# Sheet1.net
KiCad netlist of a schematic drawn in Altium Designer
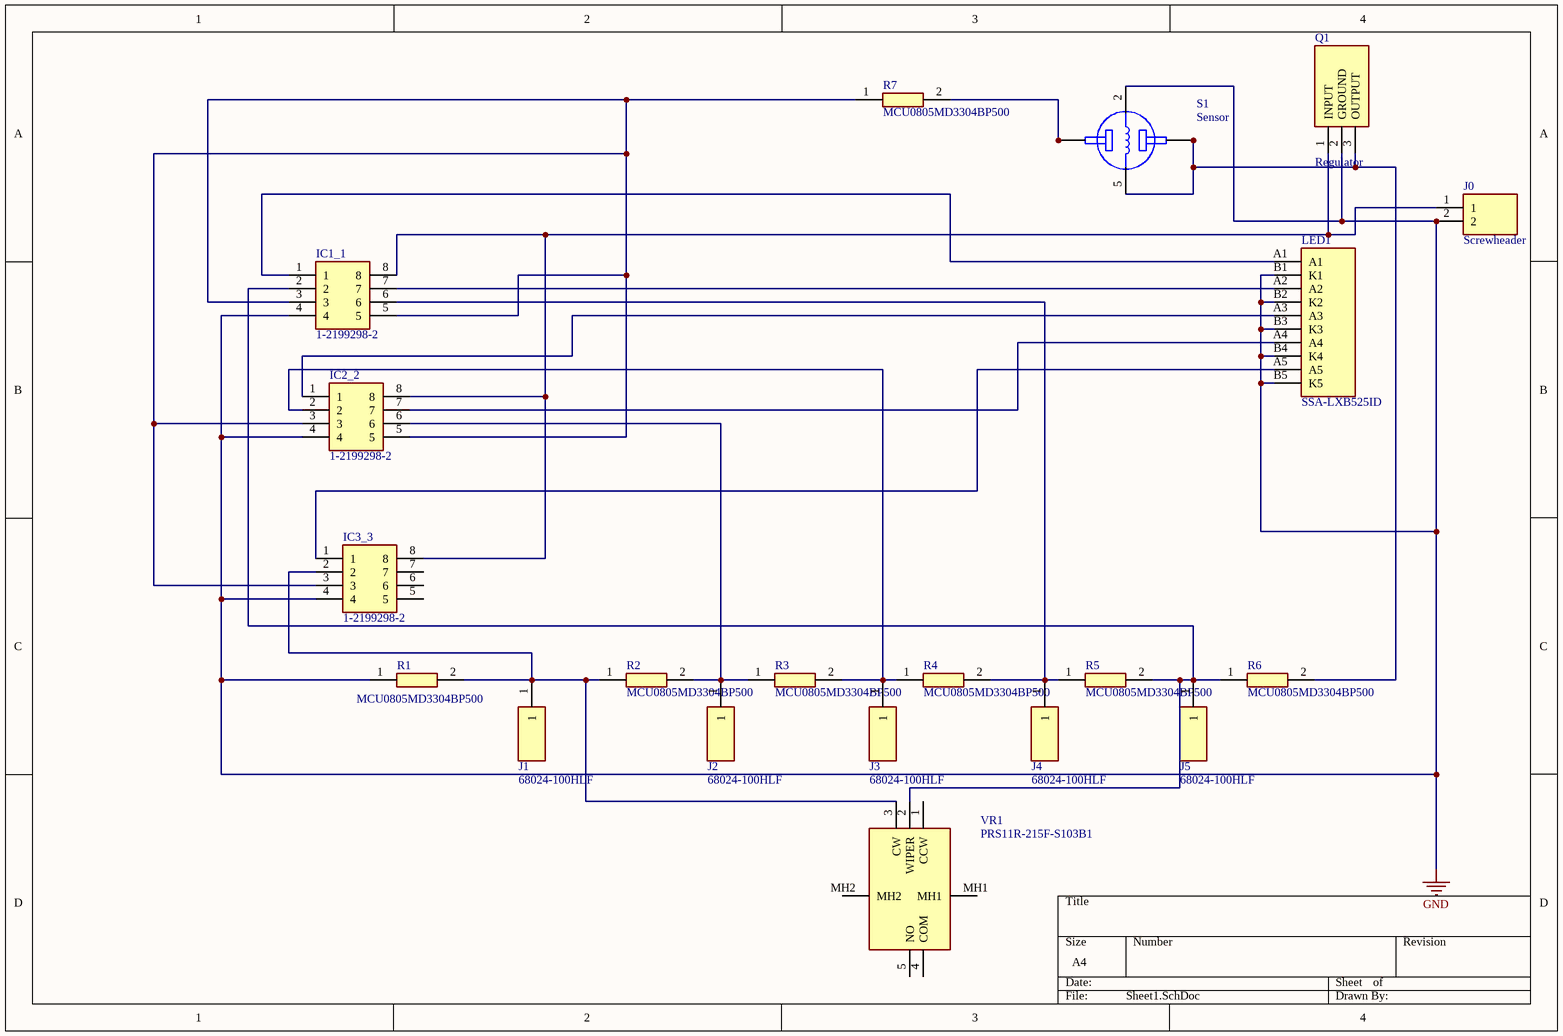
[diagram p0: Sheet1.SchDoc]

(export (version "E")
  (design (tool "Eeschema 10.0.6"))
  (components
    (comp (ref "IC1_1")
      (value "1-2199298-2")
      (footprint "SamacSys:DIPS762W70P254L1016H510Q8N")
      (description "Integrated Circuit")
      (fields (field (name "MOUSER PART NUMBER") "571-1-2199298-2"))
      (libsource (lib "SamacSys") (part "1-2199298-2"))
    )
    (comp (ref "IC2_2")
      (value "1-2199298-2")
      (footprint "SamacSys:DIPS762W70P254L1016H510Q8N")
      (description "Integrated Circuit")
      (fields (field (name "MOUSER PART NUMBER") "571-1-2199298-2"))
      (libsource (lib "SamacSys") (part "1-2199298-2"))
    )
    (comp (ref "IC3_3")
      (value "1-2199298-2")
      (footprint "SamacSys:DIPS762W70P254L1016H510Q8N")
      (description "Integrated Circuit")
      (fields (field (name "MOUSER PART NUMBER") "571-1-2199298-2"))
      (libsource (lib "SamacSys") (part "1-2199298-2"))
    )
    (comp (ref "J0")
      (value "Screwheader")
      (footprint "SamacSys:SHDR2W100P0X500_1X2_1120X800X1100P")
      (description "Connector")
      (fields
        (field (name "MANUFACTURER_PART_NUMBER") "691111710002")
        (field (name "MOUSER PART NUMBER") "710-691111710002")
      )
      (libsource (lib "SamacSys") (part "691111710002"))
    )
    (comp (ref "J1")
      (value "68024-100HLF")
      (footprint "HDRV1W67P0X254_1X1_254X241X1082P")
      (description "Connector")
      (fields (field (name "MOUSER PART NUMBER") "649-68024-100HLF"))
      (libsource (lib "*") (part "68024-100HLF"))
    )
    (comp (ref "J2")
      (value "68024-100HLF")
      (footprint "HDRV1W67P0X254_1X1_254X241X1082P")
      (description "Connector")
      (fields (field (name "MOUSER PART NUMBER") "649-68024-100HLF"))
      (libsource (lib "*") (part "68024-100HLF"))
    )
    (comp (ref "J3")
      (value "68024-100HLF")
      (footprint "HDRV1W67P0X254_1X1_254X241X1082P")
      (description "Connector")
      (fields (field (name "MOUSER PART NUMBER") "649-68024-100HLF"))
      (libsource (lib "*") (part "68024-100HLF"))
    )
    (comp (ref "J4")
      (value "68024-100HLF")
      (footprint "HDRV1W67P0X254_1X1_254X241X1082P")
      (description "Connector")
      (fields (field (name "MOUSER PART NUMBER") "649-68024-100HLF"))
      (libsource (lib "*") (part "68024-100HLF"))
    )
    (comp (ref "J5")
      (value "68024-100HLF")
      (footprint "HDRV1W67P0X254_1X1_254X241X1082P")
      (description "Connector")
      (fields (field (name "MOUSER PART NUMBER") "649-68024-100HLF"))
      (libsource (lib "*") (part "68024-100HLF"))
    )
    (comp (ref "LED1")
      (value "SSA-LXB525ID")
      (footprint "SamacSys:SSALXB525ID")
      (description "LED (Multiple)")
      (fields (field (name "MOUSER PART NUMBER") "696-SSA-LXB525ID"))
      (libsource (lib "SamacSys") (part "SSA-LXB525ID"))
    )
    (comp (ref "Q1")
      (value "Regulator")
      (footprint "SamacSys:TO255P460X1020X1968-3P")
      (description "Transistor")
      (fields
        (field (name "MANUFACTURER_PART_NUMBER") "L7805ACV-DG")
        (field (name "MOUSER PART NUMBER") "511-L7805ACV-DG")
      )
      (libsource (lib "SamacSys") (part "L7805ACV-DG"))
    )
    (comp (ref "R1")
      (value "MCU0805MD3304BP500")
      (footprint "SamacSys:RESC2012X62N")
      (description "Resistor")
      (fields (field (name "MOUSER PART NUMBER") "594-MCU0805MD3304BP5"))
      (libsource (lib "SamacSys") (part "MCU0805MD3304BP500"))
    )
    (comp (ref "R2")
      (value "MCU0805MD3304BP500")
      (footprint "SamacSys:RESC2012X62N")
      (description "Resistor")
      (fields (field (name "MOUSER PART NUMBER") "594-MCU0805MD3304BP5"))
      (libsource (lib "SamacSys") (part "MCU0805MD3304BP500"))
    )
    (comp (ref "R3")
      (value "MCU0805MD3304BP500")
      (footprint "SamacSys:RESC2012X62N")
      (description "Resistor")
      (fields (field (name "MOUSER PART NUMBER") "594-MCU0805MD3304BP5"))
      (libsource (lib "SamacSys") (part "MCU0805MD3304BP500"))
    )
    (comp (ref "R4")
      (value "MCU0805MD3304BP500")
      (footprint "SamacSys:RESC2012X62N")
      (description "Resistor")
      (fields (field (name "MOUSER PART NUMBER") "594-MCU0805MD3304BP5"))
      (libsource (lib "SamacSys") (part "MCU0805MD3304BP500"))
    )
    (comp (ref "R5")
      (value "MCU0805MD3304BP500")
      (footprint "SamacSys:RESC2012X62N")
      (description "Resistor")
      (fields (field (name "MOUSER PART NUMBER") "594-MCU0805MD3304BP5"))
      (libsource (lib "SamacSys") (part "MCU0805MD3304BP500"))
    )
    (comp (ref "R6")
      (value "MCU0805MD3304BP500")
      (footprint "SamacSys:RESC2012X62N")
      (description "Resistor")
      (fields (field (name "MOUSER PART NUMBER") "594-MCU0805MD3304BP5"))
      (libsource (lib "SamacSys") (part "MCU0805MD3304BP500"))
    )
    (comp (ref "R7")
      (value "MCU0805MD3304BP500")
      (footprint "SamacSys:RESC2012X62N")
      (description "Resistor")
      (fields (field (name "MOUSER PART NUMBER") "594-MCU0805MD3304BP5"))
      (libsource (lib "SamacSys") (part "MCU0805MD3304BP500"))
    )
    (comp (ref "S1")
      (value "Sensor")
      (footprint "XDCR_SEN-08880")
      (libsource (lib "SamacSys") (part "Sensor"))
    )
    (comp (ref "VR1")
      (value "PRS11R-215F-S103B1")
      (footprint "SamacSys:PRS11R215FS103B1")
      (description "Variable Resistor")
      (fields (field (name "MOUSER PART NUMBER") "652-PRS11R215FS103B1"))
      (libsource (lib "SamacSys") (part "PRS11R-215F-S103B1"))
    )
  )
  (nets
    (net (code "1") (name "GND") (class "Default")
      (node (ref "IC1_1") (pin "4") (pinfunction "4_4") (pintype "passive"))
      (node (ref "IC2_2") (pin "4") (pinfunction "4_4") (pintype "passive"))
      (node (ref "IC3_3") (pin "4") (pinfunction "4_4") (pintype "passive"))
      (node (ref "J0") (pin "2") (pinfunction "2_2") (pintype "passive"))
      (node (ref "LED1") (pin "B1") (pinfunction "K1_B1") (pintype "passive"))
      (node (ref "LED1") (pin "B2") (pinfunction "K2_B2") (pintype "passive"))
      (node (ref "LED1") (pin "B3") (pinfunction "K3_B3") (pintype "passive"))
      (node (ref "LED1") (pin "B4") (pinfunction "K4_B4") (pintype "passive"))
      (node (ref "LED1") (pin "B5") (pinfunction "K5_B5") (pintype "passive"))
      (node (ref "Q1") (pin "2") (pinfunction "GROUND_2") (pintype "passive"))
      (node (ref "R1") (pin "1") (pinfunction "1_1") (pintype "passive"))
      (node (ref "S1") (pin "2") (pinfunction "H1_2") (pintype "passive"))
    )
    (net (code "2") (name "Net-(IC1_1-Pad1)") (class "Default")
      (node (ref "IC1_1") (pin "1") (pinfunction "1_1") (pintype "passive"))
      (node (ref "LED1") (pin "A1") (pinfunction "A1_A1") (pintype "passive"))
    )
    (net (code "3") (name "Net-(IC1_1-Pad3)") (class "Default")
      (node (ref "IC1_1") (pin "3") (pinfunction "3_3") (pintype "passive"))
      (node (ref "IC1_1") (pin "5") (pinfunction "5_5") (pintype "passive"))
      (node (ref "IC2_2") (pin "3") (pinfunction "3_3") (pintype "passive"))
      (node (ref "IC2_2") (pin "5") (pinfunction "5_5") (pintype "passive"))
      (node (ref "IC3_3") (pin "3") (pinfunction "3_3") (pintype "passive"))
      (node (ref "R7") (pin "1") (pinfunction "1_1") (pintype "passive"))
    )
    (net (code "4") (name "Net-(IC1_1-Pad6)") (class "Default")
      (node (ref "IC1_1") (pin "6") (pinfunction "6_6") (pintype "passive"))
      (node (ref "J4") (pin "1") (pinfunction "1_1") (pintype "passive"))
      (node (ref "R4") (pin "2") (pinfunction "2_2") (pintype "passive"))
      (node (ref "R5") (pin "1") (pinfunction "1_1") (pintype "passive"))
    )
    (net (code "5") (name "Net-(IC1_1-Pad7)") (class "Default")
      (node (ref "IC1_1") (pin "7") (pinfunction "7_7") (pintype "passive"))
      (node (ref "LED1") (pin "A2") (pinfunction "A2_A2") (pintype "passive"))
    )
    (net (code "6") (name "Net-(IC2_2-Pad1)") (class "Default")
      (node (ref "IC2_2") (pin "1") (pinfunction "1_1") (pintype "passive"))
      (node (ref "LED1") (pin "A3") (pinfunction "A3_A3") (pintype "passive"))
    )
    (net (code "7") (name "Net-(IC2_2-Pad2)") (class "Default")
      (node (ref "IC2_2") (pin "2") (pinfunction "2_2") (pintype "passive"))
      (node (ref "J3") (pin "1") (pinfunction "1_1") (pintype "passive"))
      (node (ref "R3") (pin "2") (pinfunction "2_2") (pintype "passive"))
      (node (ref "R4") (pin "1") (pinfunction "1_1") (pintype "passive"))
    )
    (net (code "8") (name "Net-(IC2_2-Pad6)") (class "Default")
      (node (ref "IC2_2") (pin "6") (pinfunction "6_6") (pintype "passive"))
      (node (ref "J2") (pin "1") (pinfunction "1_1") (pintype "passive"))
      (node (ref "R2") (pin "2") (pinfunction "2_2") (pintype "passive"))
      (node (ref "R3") (pin "1") (pinfunction "1_1") (pintype "passive"))
    )
    (net (code "9") (name "Net-(IC2_2-Pad7)") (class "Default")
      (node (ref "IC2_2") (pin "7") (pinfunction "7_7") (pintype "passive"))
      (node (ref "LED1") (pin "A4") (pinfunction "A4_A4") (pintype "passive"))
    )
    (net (code "10") (name "Net-(IC3_3-Pad1)") (class "Default")
      (node (ref "IC3_3") (pin "1") (pinfunction "1_1") (pintype "passive"))
      (node (ref "LED1") (pin "A5") (pinfunction "A5_A5") (pintype "passive"))
    )
    (net (code "11") (name "Net-(Q1-INPUT)") (class "Default")
      (node (ref "IC1_1") (pin "8") (pinfunction "8_8") (pintype "passive"))
      (node (ref "IC2_2") (pin "8") (pinfunction "8_8") (pintype "passive"))
      (node (ref "IC3_3") (pin "8") (pinfunction "8_8") (pintype "passive"))
      (node (ref "J0") (pin "1") (pinfunction "1_1") (pintype "passive"))
      (node (ref "Q1") (pin "1") (pinfunction "INPUT_1") (pintype "passive"))
    )
    (net (code "12") (name "Net-(Q1-OUTPUT)") (class "Default")
      (node (ref "Q1") (pin "3") (pinfunction "OUTPUT_3") (pintype "passive"))
      (node (ref "R6") (pin "2") (pinfunction "2_2") (pintype "passive"))
      (node (ref "S1") (pin "4") (pinfunction "B_4") (pintype "passive"))
      (node (ref "S1") (pin "5") (pinfunction "H2_5") (pintype "passive"))
      (node (ref "S1") (pin "6") (pinfunction "B_6") (pintype "passive"))
    )
    (net (code "13") (name "Net-(R7-Pad2)") (class "Default")
      (node (ref "R7") (pin "2") (pinfunction "2_2") (pintype "passive"))
      (node (ref "S1") (pin "1") (pinfunction "A_1") (pintype "passive"))
      (node (ref "S1") (pin "3") (pinfunction "A_3") (pintype "passive"))
    )
    (net (code "14") (name "Net-(VR1-CW)") (class "Default")
      (node (ref "IC3_3") (pin "2") (pinfunction "2_2") (pintype "passive"))
      (node (ref "J1") (pin "1") (pinfunction "1_1") (pintype "passive"))
      (node (ref "R1") (pin "2") (pinfunction "2_2") (pintype "passive"))
      (node (ref "R2") (pin "1") (pinfunction "1_1") (pintype "passive"))
      (node (ref "VR1") (pin "3") (pinfunction "CW_3") (pintype "passive"))
    )
    (net (code "15") (name "Net-(VR1-WIPER)") (class "Default")
      (node (ref "IC1_1") (pin "2") (pinfunction "2_2") (pintype "passive"))
      (node (ref "J5") (pin "1") (pinfunction "1_1") (pintype "passive"))
      (node (ref "R5") (pin "2") (pinfunction "2_2") (pintype "passive"))
      (node (ref "R6") (pin "1") (pinfunction "1_1") (pintype "passive"))
      (node (ref "VR1") (pin "2") (pinfunction "WIPER_2") (pintype "passive"))
    )
    (net (code "16") (name "unconnected-(IC3_3-Pad5)") (class "Default")
      (node (ref "IC3_3") (pin "5") (pinfunction "5_5") (pintype "passive"))
    )
    (net (code "17") (name "unconnected-(IC3_3-Pad6)") (class "Default")
      (node (ref "IC3_3") (pin "6") (pinfunction "6_6") (pintype "passive"))
    )
    (net (code "18") (name "unconnected-(IC3_3-Pad7)") (class "Default")
      (node (ref "IC3_3") (pin "7") (pinfunction "7_7") (pintype "passive"))
    )
    (net (code "19") (name "unconnected-(VR1-CCW-Pad1)") (class "Default")
      (node (ref "VR1") (pin "1") (pinfunction "CCW_1") (pintype "passive"))
    )
    (net (code "20") (name "unconnected-(VR1-COM-Pad4)") (class "Default")
      (node (ref "VR1") (pin "4") (pinfunction "COM_4") (pintype "passive"))
    )
    (net (code "21") (name "unconnected-(VR1-NO-Pad5)") (class "Default")
      (node (ref "VR1") (pin "5") (pinfunction "NO_5") (pintype "passive"))
    )
    (net (code "22") (name "unconnected-(VR1-PadMH1)") (class "Default")
      (node (ref "VR1") (pin "MH1") (pinfunction "MH1_MH1") (pintype "passive"))
    )
    (net (code "23") (name "unconnected-(VR1-PadMH2)") (class "Default")
      (node (ref "VR1") (pin "MH2") (pinfunction "MH2_MH2") (pintype "passive"))
    )
  )
)
